# Leak_Detector_2B.net
KiCad netlist of a schematic drawn in EAGLE
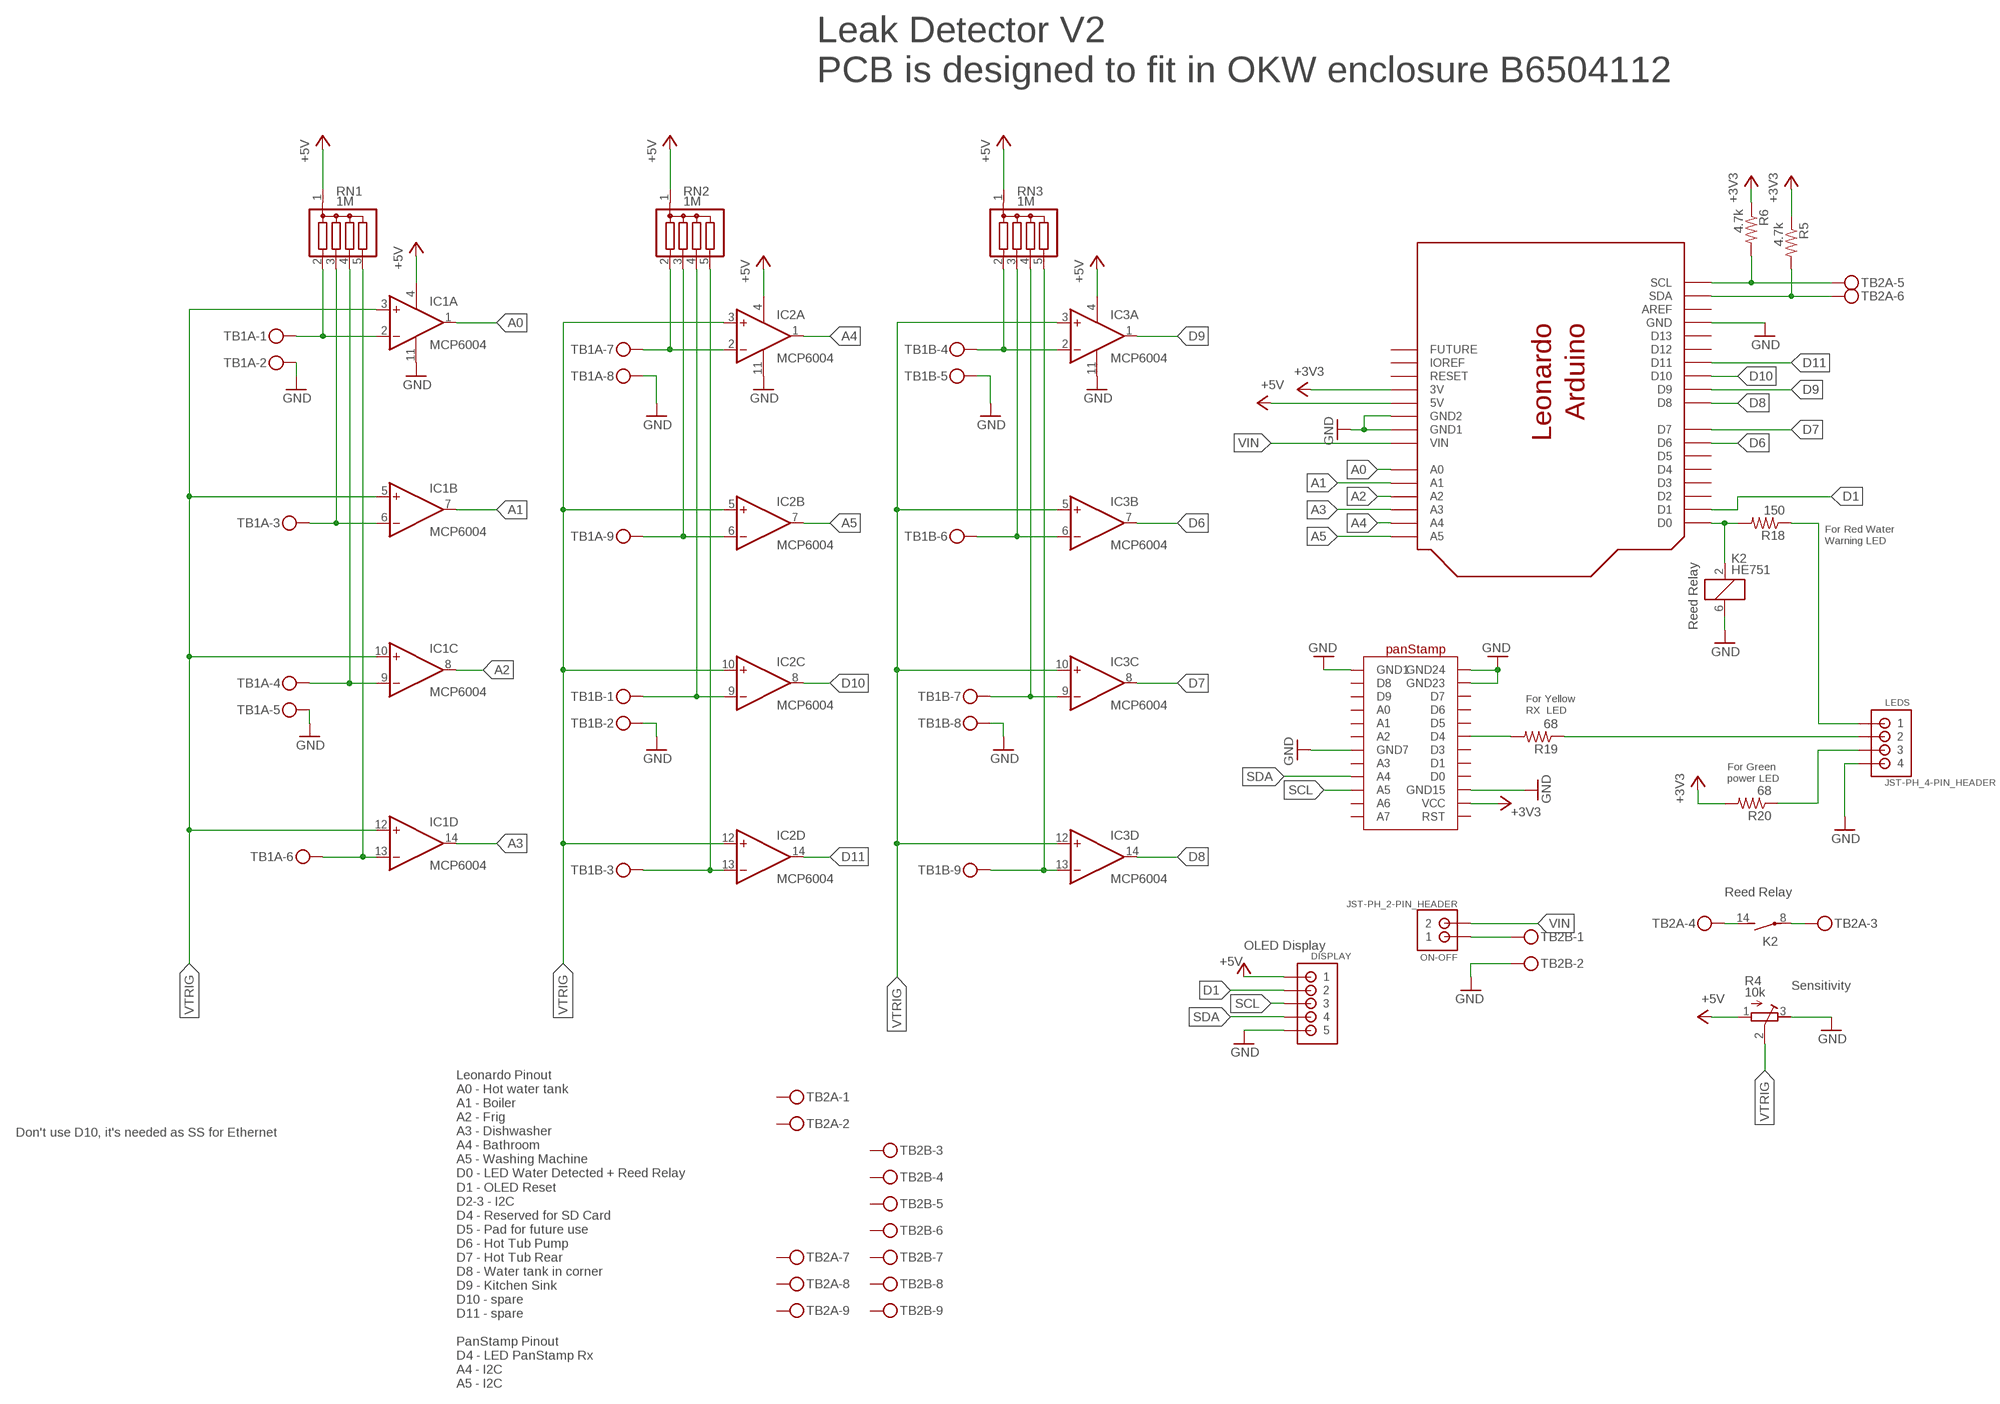
[diagram p0: schematic, sheet 1]

(export (version "E")
  (design (tool "Eeschema 10.0.6"))
  (components
    (comp (ref "DISPLAY")
      (value "JST-PH_5-PIN_HEADER")
      (footprint "eagle-import:JST_B5B-PH_HEADER")
      (libsource (lib "eagle-import") (part "JST-PH_5-PIN_HEADER"))
    )
    (comp (ref "IC1")
      (value "MCP6004")
      (footprint "eagle-import:DIL14")
      (libsource (lib "eagle-import") (part "MCP604P"))
    )
    (comp (ref "IC2")
      (value "MCP6004")
      (footprint "eagle-import:DIL14")
      (libsource (lib "eagle-import") (part "MCP604P"))
    )
    (comp (ref "IC3")
      (value "MCP6004")
      (footprint "eagle-import:DIL14")
      (libsource (lib "eagle-import") (part "MCP604P"))
    )
    (comp (ref "K2")
      (value "HE751")
      (footprint "eagle-import:HE751")
      (libsource (lib "eagle-import") (part "HE751"))
    )
    (comp (ref "LEDS")
      (value "JST-PH_4-PIN_HEADER")
      (footprint "eagle-import:JST_B4B-PH_HEADER")
      (libsource (lib "eagle-import") (part "JST-PH_4-PIN_HEADER"))
    )
    (comp (ref "ON-OFF")
      (value "JST-PH_2-PIN_HEADER")
      (footprint "eagle-import:JST_B2B-PH_HEADER")
      (libsource (lib "eagle-import") (part "JST-PH_2-PIN_HEADER"))
    )
    (comp (ref "R4")
      (value "10k")
      (footprint "eagle-import:RTRIM3296P")
      (libsource (lib "eagle-import") (part "R-TRIMM3296P"))
    )
    (comp (ref "R5")
      (value "4.7k")
      (footprint "eagle-import:0207_10")
      (libsource (lib "eagle-import") (part "R-US_0207/10"))
    )
    (comp (ref "R6")
      (value "4.7k")
      (footprint "eagle-import:0207_10")
      (libsource (lib "eagle-import") (part "R-US_0207/10"))
    )
    (comp (ref "R18")
      (value "150")
      (footprint "eagle-import:0207_10")
      (libsource (lib "eagle-import") (part "R-US_0207/10"))
    )
    (comp (ref "R19")
      (value "68")
      (footprint "eagle-import:0207_10")
      (libsource (lib "eagle-import") (part "R-US_0207/10"))
    )
    (comp (ref "R20")
      (value "68")
      (footprint "eagle-import:0207_10")
      (libsource (lib "eagle-import") (part "R-US_0207/10"))
    )
    (comp (ref "RN1")
      (value "1M")
      (footprint "eagle-import:SIL5")
      (libsource (lib "eagle-import") (part "G04R"))
    )
    (comp (ref "RN2")
      (value "1M")
      (footprint "eagle-import:SIL5")
      (libsource (lib "eagle-import") (part "G04R"))
    )
    (comp (ref "RN3")
      (value "1M")
      (footprint "eagle-import:SIL5")
      (libsource (lib "eagle-import") (part "G04R"))
    )
    (comp (ref "TB1A")
      (value "MKDSN1,5/9-5,08")
      (footprint "eagle-import:MKDSN1,5_9-5,08")
      (fields (field (name "MPN") "SMKDSN1,5/9-5,08"))
      (libsource (lib "eagle-import") (part "MKDSN1,5/9-5,08"))
    )
    (comp (ref "TB1B")
      (value "MKDSN1,5/9-5,08")
      (footprint "eagle-import:MKDSN1,5_9-5,08")
      (fields (field (name "MPN") "SMKDSN1,5/9-5,08"))
      (libsource (lib "eagle-import") (part "MKDSN1,5/9-5,08"))
    )
    (comp (ref "TB2A")
      (value "MKDSN1,5/9-5,08")
      (footprint "eagle-import:MKDSN1,5_9-5,08")
      (fields (field (name "MPN") "SMKDSN1,5/9-5,08"))
      (libsource (lib "eagle-import") (part "MKDSN1,5/9-5,08"))
    )
    (comp (ref "TB2B")
      (value "MKDSN1,5/9-5,08")
      (footprint "eagle-import:MKDSN1,5_9-5,08")
      (fields (field (name "MPN") "SMKDSN1,5/9-5,08"))
      (libsource (lib "eagle-import") (part "MKDSN1,5/9-5,08"))
    )
    (comp (ref "U$1")
      (value "ARDUINO_LEONARDO")
      (footprint "eagle-import:ARDUINO_LEONARDO")
      (libsource (lib "eagle-import") (part "ARDUINO_LEONARDO"))
    )
    (comp (ref "U$2")
      (value "PANSTAMP")
      (footprint "eagle-import:PANSTAMP")
      (libsource (lib "eagle-import") (part "PANSTAMP"))
    )
  )
  (nets
    (net (code "1") (name "+3V3") (class "Default")
      (node (ref "R20") (pin "2") (pinfunction "2_2") (pintype "passive"))
      (node (ref "R5") (pin "1") (pinfunction "1_1") (pintype "passive"))
      (node (ref "R6") (pin "1") (pinfunction "1_1") (pintype "passive"))
      (node (ref "U$1") (pin "3V") (pinfunction "3V_3V") (pintype "power_in"))
      (node (ref "U$2") (pin "VCC") (pinfunction "VCC_VCC") (pintype "power_in"))
    )
    (net (code "2") (name "+5V") (class "Default")
      (node (ref "DISPLAY") (pin "P1") (pinfunction "1_P1") (pintype "bidirectional"))
      (node (ref "IC1") (pin "4") (pinfunction "V+_4") (pintype "power_in"))
      (node (ref "IC2") (pin "4") (pinfunction "V+_4") (pintype "power_in"))
      (node (ref "IC3") (pin "4") (pinfunction "V+_4") (pintype "power_in"))
      (node (ref "R4") (pin "1") (pinfunction "E_1") (pintype "passive"))
      (node (ref "RN1") (pin "1") (pinfunction "1_1") (pintype "passive"))
      (node (ref "RN2") (pin "1") (pinfunction "1_1") (pintype "passive"))
      (node (ref "RN3") (pin "1") (pinfunction "1_1") (pintype "passive"))
      (node (ref "U$1") (pin "5V") (pinfunction "5V_5V") (pintype "power_in"))
    )
    (net (code "3") (name "A0") (class "Default")
      (node (ref "IC1") (pin "1") (pinfunction "OUT_1") (pintype "output"))
      (node (ref "U$1") (pin "A0") (pinfunction "A0_A0") (pintype "bidirectional"))
    )
    (net (code "4") (name "A1") (class "Default")
      (node (ref "IC1") (pin "7") (pinfunction "OUT_7") (pintype "output"))
      (node (ref "U$1") (pin "A1") (pinfunction "A1_A1") (pintype "bidirectional"))
    )
    (net (code "5") (name "A2") (class "Default")
      (node (ref "IC1") (pin "8") (pinfunction "OUT_8") (pintype "output"))
      (node (ref "U$1") (pin "A2") (pinfunction "A2_A2") (pintype "bidirectional"))
    )
    (net (code "6") (name "A3") (class "Default")
      (node (ref "IC1") (pin "14") (pinfunction "OUT_14") (pintype "output"))
      (node (ref "U$1") (pin "A3") (pinfunction "A3_A3") (pintype "bidirectional"))
    )
    (net (code "7") (name "A4") (class "Default")
      (node (ref "IC2") (pin "1") (pinfunction "OUT_1") (pintype "output"))
      (node (ref "U$1") (pin "A4") (pinfunction "A4_A4") (pintype "bidirectional"))
    )
    (net (code "8") (name "A5") (class "Default")
      (node (ref "IC2") (pin "7") (pinfunction "OUT_7") (pintype "output"))
      (node (ref "U$1") (pin "A5") (pinfunction "A5_A5") (pintype "bidirectional"))
    )
    (net (code "9") (name "D1") (class "Default")
      (node (ref "DISPLAY") (pin "P2") (pinfunction "2_P2") (pintype "bidirectional"))
      (node (ref "U$1") (pin "D1") (pinfunction "D1_D1") (pintype "bidirectional"))
    )
    (net (code "10") (name "D6") (class "Default")
      (node (ref "IC3") (pin "7") (pinfunction "OUT_7") (pintype "output"))
      (node (ref "U$1") (pin "D6") (pinfunction "D6_D6") (pintype "bidirectional"))
    )
    (net (code "11") (name "D7") (class "Default")
      (node (ref "IC3") (pin "8") (pinfunction "OUT_8") (pintype "output"))
      (node (ref "U$1") (pin "D7") (pinfunction "D7_D7") (pintype "bidirectional"))
    )
    (net (code "12") (name "D8") (class "Default")
      (node (ref "IC3") (pin "14") (pinfunction "OUT_14") (pintype "output"))
      (node (ref "U$1") (pin "D8") (pinfunction "D8_D8") (pintype "bidirectional"))
    )
    (net (code "13") (name "D9") (class "Default")
      (node (ref "IC3") (pin "1") (pinfunction "OUT_1") (pintype "output"))
      (node (ref "U$1") (pin "D9") (pinfunction "D9_D9") (pintype "bidirectional"))
    )
    (net (code "14") (name "D10") (class "Default")
      (node (ref "IC2") (pin "8") (pinfunction "OUT_8") (pintype "output"))
      (node (ref "U$1") (pin "D10") (pinfunction "D10_D10") (pintype "bidirectional"))
    )
    (net (code "15") (name "D11") (class "Default")
      (node (ref "IC2") (pin "14") (pinfunction "OUT_14") (pintype "output"))
      (node (ref "U$1") (pin "D11") (pinfunction "D11_D11") (pintype "bidirectional"))
    )
    (net (code "16") (name "GND") (class "Default")
      (node (ref "DISPLAY") (pin "P5") (pinfunction "5_P5") (pintype "bidirectional"))
      (node (ref "IC1") (pin "11") (pinfunction "V-_11") (pintype "power_in"))
      (node (ref "IC2") (pin "11") (pinfunction "V-_11") (pintype "power_in"))
      (node (ref "IC3") (pin "11") (pinfunction "V-_11") (pintype "power_in"))
      (node (ref "K2") (pin "6") (pinfunction "2_6") (pintype "passive"))
      (node (ref "LEDS") (pin "P4") (pinfunction "4_P4") (pintype "bidirectional"))
      (node (ref "R4") (pin "3") (pinfunction "A_3") (pintype "passive"))
      (node (ref "TB1A") (pin "2") (pinfunction "KL_2") (pintype "passive"))
      (node (ref "TB1A") (pin "5") (pinfunction "KL_5") (pintype "passive"))
      (node (ref "TB1A") (pin "8") (pinfunction "KL_8") (pintype "passive"))
      (node (ref "TB1B") (pin "2") (pinfunction "KL_2") (pintype "passive"))
      (node (ref "TB1B") (pin "5") (pinfunction "KL_5") (pintype "passive"))
      (node (ref "TB1B") (pin "8") (pinfunction "KL_8") (pintype "passive"))
      (node (ref "TB2B") (pin "2") (pinfunction "KL_2") (pintype "passive"))
      (node (ref "U$1") (pin "GND") (pinfunction "GND_GND") (pintype "power_in"))
      (node (ref "U$1") (pin "GND$2") (pinfunction "GND2_GND$2") (pintype "power_in"))
      (node (ref "U$1") (pin "GND$3") (pinfunction "GND1_GND$3") (pintype "power_in"))
      (node (ref "U$2") (pin "GND1") (pinfunction "GND1_GND1") (pintype "power_in"))
      (node (ref "U$2") (pin "GND15") (pinfunction "GND15_GND15") (pintype "power_in"))
      (node (ref "U$2") (pin "GND23") (pinfunction "GND23_GND23") (pintype "power_in"))
      (node (ref "U$2") (pin "GND24") (pinfunction "GND24_GND24") (pintype "power_in"))
      (node (ref "U$2") (pin "GND7") (pinfunction "GND7_GND7") (pintype "power_in"))
    )
    (net (code "17") (name "Net-(IC1A--IN)") (class "Default")
      (node (ref "IC1") (pin "2") (pinfunction "-IN_2") (pintype "input"))
      (node (ref "RN1") (pin "2") (pinfunction "2_2") (pintype "passive"))
      (node (ref "TB1A") (pin "1") (pinfunction "KL_1") (pintype "passive"))
    )
    (net (code "18") (name "Net-(IC1B--IN)") (class "Default")
      (node (ref "IC1") (pin "6") (pinfunction "-IN_6") (pintype "input"))
      (node (ref "RN1") (pin "3") (pinfunction "3_3") (pintype "passive"))
      (node (ref "TB1A") (pin "3") (pinfunction "KL_3") (pintype "passive"))
    )
    (net (code "19") (name "Net-(IC1C--IN)") (class "Default")
      (node (ref "IC1") (pin "9") (pinfunction "-IN_9") (pintype "input"))
      (node (ref "RN1") (pin "4") (pinfunction "4_4") (pintype "passive"))
      (node (ref "TB1A") (pin "4") (pinfunction "KL_4") (pintype "passive"))
    )
    (net (code "20") (name "Net-(IC1D--IN)") (class "Default")
      (node (ref "IC1") (pin "13") (pinfunction "-IN_13") (pintype "input"))
      (node (ref "RN1") (pin "5") (pinfunction "5_5") (pintype "passive"))
      (node (ref "TB1A") (pin "6") (pinfunction "KL_6") (pintype "passive"))
    )
    (net (code "21") (name "Net-(IC2A--IN)") (class "Default")
      (node (ref "IC2") (pin "2") (pinfunction "-IN_2") (pintype "input"))
      (node (ref "RN2") (pin "2") (pinfunction "2_2") (pintype "passive"))
      (node (ref "TB1A") (pin "7") (pinfunction "KL_7") (pintype "passive"))
    )
    (net (code "22") (name "Net-(IC2B--IN)") (class "Default")
      (node (ref "IC2") (pin "6") (pinfunction "-IN_6") (pintype "input"))
      (node (ref "RN2") (pin "3") (pinfunction "3_3") (pintype "passive"))
      (node (ref "TB1A") (pin "9") (pinfunction "KL_9") (pintype "passive"))
    )
    (net (code "23") (name "Net-(IC2C--IN)") (class "Default")
      (node (ref "IC2") (pin "9") (pinfunction "-IN_9") (pintype "input"))
      (node (ref "RN2") (pin "4") (pinfunction "4_4") (pintype "passive"))
      (node (ref "TB1B") (pin "1") (pinfunction "KL_1") (pintype "passive"))
    )
    (net (code "24") (name "Net-(IC2D--IN)") (class "Default")
      (node (ref "IC2") (pin "13") (pinfunction "-IN_13") (pintype "input"))
      (node (ref "RN2") (pin "5") (pinfunction "5_5") (pintype "passive"))
      (node (ref "TB1B") (pin "3") (pinfunction "KL_3") (pintype "passive"))
    )
    (net (code "25") (name "Net-(IC3A--IN)") (class "Default")
      (node (ref "IC3") (pin "2") (pinfunction "-IN_2") (pintype "input"))
      (node (ref "RN3") (pin "2") (pinfunction "2_2") (pintype "passive"))
      (node (ref "TB1B") (pin "4") (pinfunction "KL_4") (pintype "passive"))
    )
    (net (code "26") (name "Net-(IC3B--IN)") (class "Default")
      (node (ref "IC3") (pin "6") (pinfunction "-IN_6") (pintype "input"))
      (node (ref "RN3") (pin "3") (pinfunction "3_3") (pintype "passive"))
      (node (ref "TB1B") (pin "6") (pinfunction "KL_6") (pintype "passive"))
    )
    (net (code "27") (name "Net-(IC3C--IN)") (class "Default")
      (node (ref "IC3") (pin "9") (pinfunction "-IN_9") (pintype "input"))
      (node (ref "RN3") (pin "4") (pinfunction "4_4") (pintype "passive"))
      (node (ref "TB1B") (pin "7") (pinfunction "KL_7") (pintype "passive"))
    )
    (net (code "28") (name "Net-(IC3D--IN)") (class "Default")
      (node (ref "IC3") (pin "13") (pinfunction "-IN_13") (pintype "input"))
      (node (ref "RN3") (pin "5") (pinfunction "5_5") (pintype "passive"))
      (node (ref "TB1B") (pin "9") (pinfunction "KL_9") (pintype "passive"))
    )
    (net (code "29") (name "Net-(K2A-1)") (class "Default")
      (node (ref "K2") (pin "2") (pinfunction "1_2") (pintype "passive"))
      (node (ref "R18") (pin "2") (pinfunction "2_2") (pintype "passive"))
      (node (ref "U$1") (pin "D0") (pinfunction "D0_D0") (pintype "bidirectional"))
    )
    (net (code "30") (name "Net-(K2B-P)") (class "Default")
      (node (ref "K2") (pin "8") (pinfunction "P_8") (pintype "passive"))
      (node (ref "TB2A") (pin "3") (pinfunction "KL_3") (pintype "passive"))
    )
    (net (code "31") (name "Net-(K2B-S)") (class "Default")
      (node (ref "K2") (pin "14") (pinfunction "S_14") (pintype "passive"))
      (node (ref "TB2A") (pin "4") (pinfunction "KL_4") (pintype "passive"))
    )
    (net (code "32") (name "Net-(LEDS-1)") (class "Default")
      (node (ref "LEDS") (pin "P1") (pinfunction "1_P1") (pintype "bidirectional"))
      (node (ref "R18") (pin "1") (pinfunction "1_1") (pintype "passive"))
    )
    (net (code "33") (name "Net-(LEDS-2)") (class "Default")
      (node (ref "LEDS") (pin "P2") (pinfunction "2_P2") (pintype "bidirectional"))
      (node (ref "R19") (pin "1") (pinfunction "1_1") (pintype "passive"))
    )
    (net (code "34") (name "Net-(LEDS-3)") (class "Default")
      (node (ref "LEDS") (pin "P3") (pinfunction "3_P3") (pintype "bidirectional"))
      (node (ref "R20") (pin "1") (pinfunction "1_1") (pintype "passive"))
    )
    (net (code "35") (name "Net-(ON-OFF-1)") (class "Default")
      (node (ref "ON-OFF") (pin "P1") (pinfunction "1_P1") (pintype "bidirectional"))
      (node (ref "TB2B") (pin "1") (pinfunction "KL_1") (pintype "passive"))
    )
    (net (code "36") (name "Net-(R19-Pad2)") (class "Default")
      (node (ref "R19") (pin "2") (pinfunction "2_2") (pintype "passive"))
      (node (ref "U$2") (pin "D4") (pinfunction "D4_D4") (pintype "bidirectional"))
    )
    (net (code "37") (name "SCL") (class "Default")
      (node (ref "DISPLAY") (pin "P3") (pinfunction "3_P3") (pintype "bidirectional"))
      (node (ref "R6") (pin "2") (pinfunction "2_2") (pintype "passive"))
      (node (ref "TB2A") (pin "5") (pinfunction "KL_5") (pintype "passive"))
      (node (ref "U$1") (pin "SCL") (pinfunction "SCL_SCL") (pintype "bidirectional"))
      (node (ref "U$2") (pin "A5") (pinfunction "A5_A5") (pintype "bidirectional"))
    )
    (net (code "38") (name "SDA") (class "Default")
      (node (ref "DISPLAY") (pin "P4") (pinfunction "4_P4") (pintype "bidirectional"))
      (node (ref "R5") (pin "2") (pinfunction "2_2") (pintype "passive"))
      (node (ref "TB2A") (pin "6") (pinfunction "KL_6") (pintype "passive"))
      (node (ref "U$1") (pin "SDA") (pinfunction "SDA_SDA") (pintype "bidirectional"))
      (node (ref "U$2") (pin "A4") (pinfunction "A4_A4") (pintype "bidirectional"))
    )
    (net (code "39") (name "VIN") (class "Default")
      (node (ref "ON-OFF") (pin "P2") (pinfunction "2_P2") (pintype "bidirectional"))
      (node (ref "U$1") (pin "VIN") (pinfunction "VIN_VIN") (pintype "power_in"))
    )
    (net (code "40") (name "VTRIG") (class "Default")
      (node (ref "IC1") (pin "10") (pinfunction "+IN_10") (pintype "input"))
      (node (ref "IC1") (pin "12") (pinfunction "+IN_12") (pintype "input"))
      (node (ref "IC1") (pin "3") (pinfunction "+IN_3") (pintype "input"))
      (node (ref "IC1") (pin "5") (pinfunction "+IN_5") (pintype "input"))
      (node (ref "IC2") (pin "10") (pinfunction "+IN_10") (pintype "input"))
      (node (ref "IC2") (pin "12") (pinfunction "+IN_12") (pintype "input"))
      (node (ref "IC2") (pin "3") (pinfunction "+IN_3") (pintype "input"))
      (node (ref "IC2") (pin "5") (pinfunction "+IN_5") (pintype "input"))
      (node (ref "IC3") (pin "10") (pinfunction "+IN_10") (pintype "input"))
      (node (ref "IC3") (pin "12") (pinfunction "+IN_12") (pintype "input"))
      (node (ref "IC3") (pin "3") (pinfunction "+IN_3") (pintype "input"))
      (node (ref "IC3") (pin "5") (pinfunction "+IN_5") (pintype "input"))
      (node (ref "R4") (pin "2") (pinfunction "S_2") (pintype "passive"))
    )
    (net (code "41") (name "unconnected-(TB2AA-KL-Pad1)") (class "Default")
      (node (ref "TB2A") (pin "1") (pinfunction "KL_1") (pintype "passive"))
    )
    (net (code "42") (name "unconnected-(TB2AB-KL-Pad2)") (class "Default")
      (node (ref "TB2A") (pin "2") (pinfunction "KL_2") (pintype "passive"))
    )
    (net (code "43") (name "unconnected-(TB2AG-KL-Pad7)") (class "Default")
      (node (ref "TB2A") (pin "7") (pinfunction "KL_7") (pintype "passive"))
    )
    (net (code "44") (name "unconnected-(TB2AH-KL-Pad8)") (class "Default")
      (node (ref "TB2A") (pin "8") (pinfunction "KL_8") (pintype "passive"))
    )
    (net (code "45") (name "unconnected-(TB2AI-KL-Pad9)") (class "Default")
      (node (ref "TB2A") (pin "9") (pinfunction "KL_9") (pintype "passive"))
    )
    (net (code "46") (name "unconnected-(TB2BC-KL-Pad3)") (class "Default")
      (node (ref "TB2B") (pin "3") (pinfunction "KL_3") (pintype "passive"))
    )
    (net (code "47") (name "unconnected-(TB2BD-KL-Pad4)") (class "Default")
      (node (ref "TB2B") (pin "4") (pinfunction "KL_4") (pintype "passive"))
    )
    (net (code "48") (name "unconnected-(TB2BE-KL-Pad5)") (class "Default")
      (node (ref "TB2B") (pin "5") (pinfunction "KL_5") (pintype "passive"))
    )
    (net (code "49") (name "unconnected-(TB2BF-KL-Pad6)") (class "Default")
      (node (ref "TB2B") (pin "6") (pinfunction "KL_6") (pintype "passive"))
    )
    (net (code "50") (name "unconnected-(TB2BG-KL-Pad7)") (class "Default")
      (node (ref "TB2B") (pin "7") (pinfunction "KL_7") (pintype "passive"))
    )
    (net (code "51") (name "unconnected-(TB2BH-KL-Pad8)") (class "Default")
      (node (ref "TB2B") (pin "8") (pinfunction "KL_8") (pintype "passive"))
    )
    (net (code "52") (name "unconnected-(TB2BI-KL-Pad9)") (class "Default")
      (node (ref "TB2B") (pin "9") (pinfunction "KL_9") (pintype "passive"))
    )
    (net (code "53") (name "unconnected-(U$1-FUTURE-PadRESERVED)") (class "Default")
      (node (ref "U$1") (pin "RESERVED") (pinfunction "FUTURE_RESERVED") (pintype "bidirectional"))
    )
    (net (code "54") (name "unconnected-(U$1-PadAREF)") (class "Default")
      (node (ref "U$1") (pin "AREF") (pinfunction "AREF_AREF") (pintype "bidirectional"))
    )
    (net (code "55") (name "unconnected-(U$1-PadD2)") (class "Default")
      (node (ref "U$1") (pin "D2") (pinfunction "D2_D2") (pintype "bidirectional"))
    )
    (net (code "56") (name "unconnected-(U$1-PadD3)") (class "Default")
      (node (ref "U$1") (pin "D3") (pinfunction "D3_D3") (pintype "bidirectional"))
    )
    (net (code "57") (name "unconnected-(U$1-PadD4)") (class "Default")
      (node (ref "U$1") (pin "D4") (pinfunction "D4_D4") (pintype "bidirectional"))
    )
    (net (code "58") (name "unconnected-(U$1-PadD5)") (class "Default")
      (node (ref "U$1") (pin "D5") (pinfunction "D5_D5") (pintype "bidirectional"))
    )
    (net (code "59") (name "unconnected-(U$1-PadD12)") (class "Default")
      (node (ref "U$1") (pin "D12") (pinfunction "D12_D12") (pintype "bidirectional"))
    )
    (net (code "60") (name "unconnected-(U$1-PadD13)") (class "Default")
      (node (ref "U$1") (pin "D13") (pinfunction "D13_D13") (pintype "bidirectional"))
    )
    (net (code "61") (name "unconnected-(U$1-PadIOREF)") (class "Default")
      (node (ref "U$1") (pin "IOREF") (pinfunction "IOREF_IOREF") (pintype "bidirectional"))
    )
    (net (code "62") (name "unconnected-(U$1-PadRESET)") (class "Default")
      (node (ref "U$1") (pin "RESET") (pinfunction "RESET_RESET") (pintype "bidirectional"))
    )
    (net (code "63") (name "unconnected-(U$2-PadA0)") (class "Default")
      (node (ref "U$2") (pin "A0") (pinfunction "A0_A0") (pintype "bidirectional"))
    )
    (net (code "64") (name "unconnected-(U$2-PadA1)") (class "Default")
      (node (ref "U$2") (pin "A1") (pinfunction "A1_A1") (pintype "bidirectional"))
    )
    (net (code "65") (name "unconnected-(U$2-PadA2)") (class "Default")
      (node (ref "U$2") (pin "A2") (pinfunction "A2_A2") (pintype "bidirectional"))
    )
    (net (code "66") (name "unconnected-(U$2-PadA3)") (class "Default")
      (node (ref "U$2") (pin "A3") (pinfunction "A3_A3") (pintype "bidirectional"))
    )
    (net (code "67") (name "unconnected-(U$2-PadA6)") (class "Default")
      (node (ref "U$2") (pin "A6") (pinfunction "A6_A6") (pintype "bidirectional"))
    )
    (net (code "68") (name "unconnected-(U$2-PadA7)") (class "Default")
      (node (ref "U$2") (pin "A7") (pinfunction "A7_A7") (pintype "bidirectional"))
    )
    (net (code "69") (name "unconnected-(U$2-PadD0)") (class "Default")
      (node (ref "U$2") (pin "D0") (pinfunction "D0_D0") (pintype "bidirectional"))
    )
    (net (code "70") (name "unconnected-(U$2-PadD1)") (class "Default")
      (node (ref "U$2") (pin "D1") (pinfunction "D1_D1") (pintype "bidirectional"))
    )
    (net (code "71") (name "unconnected-(U$2-PadD3)") (class "Default")
      (node (ref "U$2") (pin "D3") (pinfunction "D3_D3") (pintype "bidirectional"))
    )
    (net (code "72") (name "unconnected-(U$2-PadD5)") (class "Default")
      (node (ref "U$2") (pin "D5") (pinfunction "D5_D5") (pintype "bidirectional"))
    )
    (net (code "73") (name "unconnected-(U$2-PadD6)") (class "Default")
      (node (ref "U$2") (pin "D6") (pinfunction "D6_D6") (pintype "bidirectional"))
    )
    (net (code "74") (name "unconnected-(U$2-PadD7)") (class "Default")
      (node (ref "U$2") (pin "D7") (pinfunction "D7_D7") (pintype "bidirectional"))
    )
    (net (code "75") (name "unconnected-(U$2-PadD8)") (class "Default")
      (node (ref "U$2") (pin "D8") (pinfunction "D8_D8") (pintype "bidirectional"))
    )
    (net (code "76") (name "unconnected-(U$2-PadD9)") (class "Default")
      (node (ref "U$2") (pin "D9") (pinfunction "D9_D9") (pintype "bidirectional"))
    )
    (net (code "77") (name "unconnected-(U$2-RST-PadRESET)") (class "Default")
      (node (ref "U$2") (pin "RESET") (pinfunction "RST_RESET") (pintype "bidirectional"))
    )
  )
)
